# Monitor.net
KiCad netlist of a schematic drawn in EAGLE
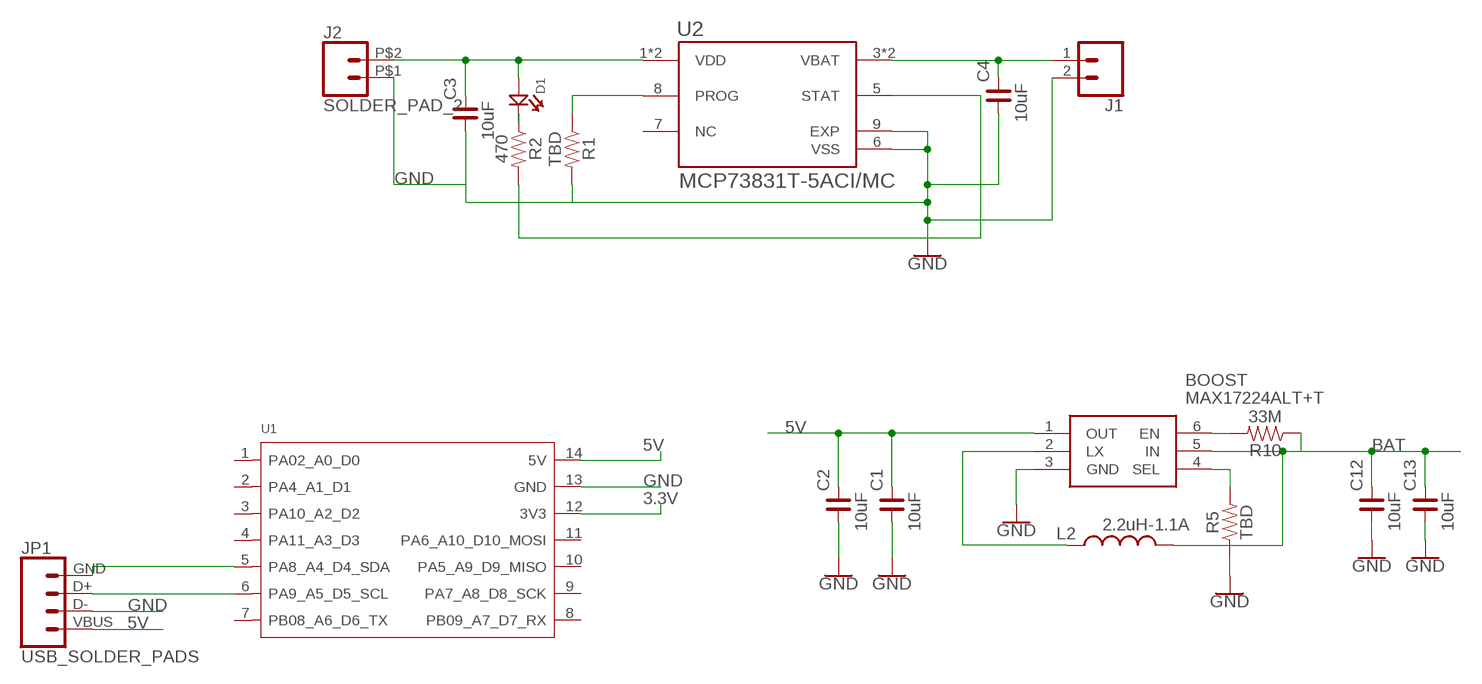
[diagram p0: schematic, sheet 1]

(export (version "E")
  (design (tool "Eeschema 10.0.6"))
  (components
    (comp (ref "BOOST")
      (value "MAX17224ALT+T")
      (footprint "eagle-import:MAX17220ALT")
      (fields (field (name "MOUSER_PART_NUMBER") "700-MAX17224ALT+T"))
      (libsource (lib "eagle-import") (part "MAX17224ALT+T"))
    )
    (comp (ref "C1")
      (value "10uF")
      (footprint "eagle-import:C0805")
      (libsource (lib "eagle-import") (part "C_0805"))
    )
    (comp (ref "C2")
      (value "10uF")
      (footprint "eagle-import:C0805")
      (libsource (lib "eagle-import") (part "C_0805"))
    )
    (comp (ref "C3")
      (value "10uF")
      (footprint "eagle-import:C0805")
      (libsource (lib "eagle-import") (part "C_0805"))
    )
    (comp (ref "C4")
      (value "10uF")
      (footprint "eagle-import:C0805")
      (libsource (lib "eagle-import") (part "C_0805"))
    )
    (comp (ref "C12")
      (value "10uF")
      (footprint "eagle-import:C0805")
      (libsource (lib "eagle-import") (part "C_0805"))
    )
    (comp (ref "C13")
      (value "10uF")
      (footprint "eagle-import:C0805")
      (libsource (lib "eagle-import") (part "C_0805"))
    )
    (comp (ref "D1")
      (value "LED0603")
      (footprint "eagle-import:LED-0603")
      (libsource (lib "eagle-import") (part "LED0603"))
    )
    (comp (ref "J1")
      (value "CONN_021X02_NO_SILK")
      (footprint "eagle-import:1X02_NO_SILK")
      (libsource (lib "eagle-import") (part "CONN_021X02_NO_SILK"))
    )
    (comp (ref "J2")
      (value "SOLDER_PAD_2")
      (footprint "eagle-import:SOLDER_PAD_2")
      (libsource (lib "eagle-import") (part "SOLDER_PAD_2"))
    )
    (comp (ref "JP1")
      (value "USB_SOLDER_PADS")
      (footprint "eagle-import:USB-SOLDER-PADS")
      (libsource (lib "eagle-import") (part "USB_SOLDER_PADS"))
    )
    (comp (ref "L2")
      (value "2.2uH-1.1A")
      (footprint "eagle-import:LPS4012")
      (fields
        (field (name "MF") "Coilcraft")
        (field (name "MPN") "LPS4012-103MRB")
        (field (name "MF_1") "BOURNS")
        (field (name "MPN_1") "SRN2009T-100M")
      )
      (libsource (lib "eagle-import") (part "L3.9X3.9_10UH_0.55A"))
    )
    (comp (ref "R1")
      (value "TBD")
      (footprint "eagle-import:0603")
      (libsource (lib "eagle-import") (part "2.2KOHM-0603-1/10W-1%"))
    )
    (comp (ref "R2")
      (value "470")
      (footprint "eagle-import:0603")
      (libsource (lib "eagle-import") (part "2.2KOHM-0603-1/10W-1%"))
    )
    (comp (ref "R5")
      (value "TBD")
      (footprint "eagle-import:0603")
      (libsource (lib "eagle-import") (part "2.2KOHM-0603-1/10W-1%"))
    )
    (comp (ref "R10")
      (value "33M")
      (footprint "eagle-import:0603")
      (libsource (lib "eagle-import") (part "2.2KOHM-0603-1/10W-1%"))
    )
    (comp (ref "U1")
      (value "MOUDLE-SEEEDUINO-XIAO")
      (footprint "eagle-import:MOUDLE14P-2.54-21X17.8MM")
      (libsource (lib "eagle-import") (part "MOUDLE-SEEEDUINO-XIAO"))
    )
    (comp (ref "U2")
      (value "MCP73831T-5ACI/MC")
      (footprint "eagle-import:SON50P200X300X100-9N")
      (fields (field (name "MF") "Microchip Technology") (field (name "MP") "MCP73831T5ACIMC"))
      (libsource (lib "eagle-import") (part "MCP73831T-5ACI/MC"))
    )
  )
  (nets
    (net (code "1") (name "/3.3V") (class "Default")
      (node (ref "U1") (pin "12") (pinfunction "3V3_12") (pintype "bidirectional"))
    )
    (net (code "2") (name "/5V") (class "Default")
      (node (ref "BOOST") (pin "1") (pinfunction "OUT_1") (pintype "bidirectional"))
      (node (ref "C1") (pin "2") (pinfunction "2_2") (pintype "passive"))
      (node (ref "C2") (pin "2") (pinfunction "2_2") (pintype "passive"))
      (node (ref "JP1") (pin "VBUS") (pinfunction "1_VBUS") (pintype "passive"))
      (node (ref "U1") (pin "14") (pinfunction "5V_14") (pintype "bidirectional"))
    )
    (net (code "3") (name "/BAT") (class "Default")
      (node (ref "BOOST") (pin "5") (pinfunction "IN_5") (pintype "bidirectional"))
      (node (ref "C12") (pin "2") (pinfunction "2_2") (pintype "passive"))
      (node (ref "C13") (pin "2") (pinfunction "2_2") (pintype "passive"))
      (node (ref "L2") (pin "2") (pinfunction "2_2") (pintype "passive"))
      (node (ref "R10") (pin "1") (pinfunction "1_1") (pintype "passive"))
    )
    (net (code "4") (name "GND") (class "Default")
      (node (ref "BOOST") (pin "3") (pinfunction "GND_3") (pintype "bidirectional"))
      (node (ref "C1") (pin "1") (pinfunction "1_1") (pintype "passive"))
      (node (ref "C12") (pin "1") (pinfunction "1_1") (pintype "passive"))
      (node (ref "C13") (pin "1") (pinfunction "1_1") (pintype "passive"))
      (node (ref "C2") (pin "1") (pinfunction "1_1") (pintype "passive"))
      (node (ref "C3") (pin "1") (pinfunction "1_1") (pintype "passive"))
      (node (ref "C4") (pin "1") (pinfunction "1_1") (pintype "passive"))
      (node (ref "J1") (pin "2") (pinfunction "2_2") (pintype "passive"))
      (node (ref "J2") (pin "P$1") (pinfunction "1_P$1") (pintype "passive"))
      (node (ref "JP1") (pin "D-") (pinfunction "2_D-") (pintype "passive"))
      (node (ref "R1") (pin "2") (pinfunction "2_2") (pintype "passive"))
      (node (ref "R5") (pin "1") (pinfunction "1_1") (pintype "passive"))
      (node (ref "U1") (pin "13") (pinfunction "GND_13") (pintype "bidirectional"))
      (node (ref "U2") (pin "6") (pinfunction "VSS_6") (pintype "power_in"))
      (node (ref "U2") (pin "9") (pinfunction "EXP_9") (pintype "power_in"))
    )
    (net (code "5") (name "Net-(BOOST-EN)") (class "Default")
      (node (ref "BOOST") (pin "6") (pinfunction "EN_6") (pintype "bidirectional"))
      (node (ref "R10") (pin "2") (pinfunction "2_2") (pintype "passive"))
    )
    (net (code "6") (name "Net-(BOOST-LX)") (class "Default")
      (node (ref "BOOST") (pin "2") (pinfunction "LX_2") (pintype "bidirectional"))
      (node (ref "L2") (pin "1") (pinfunction "1_1") (pintype "passive"))
    )
    (net (code "7") (name "Net-(BOOST-SEL)") (class "Default")
      (node (ref "BOOST") (pin "4") (pinfunction "SEL_4") (pintype "bidirectional"))
      (node (ref "R5") (pin "2") (pinfunction "2_2") (pintype "passive"))
    )
    (net (code "8") (name "Net-(C4-Pad2)") (class "Default")
      (node (ref "C4") (pin "2") (pinfunction "2_2") (pintype "passive"))
      (node (ref "J1") (pin "1") (pinfunction "1_1") (pintype "passive"))
      (node (ref "U2") (pin "3") (pinfunction "VBAT_3") (pintype "output"))
      (node (ref "U2") (pin "4") (pinfunction "VBAT_4") (pintype "output"))
    )
    (net (code "9") (name "Net-(D1-Pad-)") (class "Default")
      (node (ref "D1") (pin "-") (pinfunction "-_-") (pintype "passive"))
      (node (ref "R2") (pin "1") (pinfunction "1_1") (pintype "passive"))
    )
    (net (code "10") (name "Net-(J2-2)") (class "Default")
      (node (ref "C3") (pin "2") (pinfunction "2_2") (pintype "passive"))
      (node (ref "D1") (pin "+") (pinfunction "+_+") (pintype "passive"))
      (node (ref "J2") (pin "P$2") (pinfunction "2_P$2") (pintype "passive"))
      (node (ref "U2") (pin "1") (pinfunction "VDD_1") (pintype "input"))
      (node (ref "U2") (pin "2") (pinfunction "VDD_2") (pintype "input"))
    )
    (net (code "11") (name "Net-(JP1-3)") (class "Default")
      (node (ref "JP1") (pin "D+") (pinfunction "3_D+") (pintype "passive"))
      (node (ref "U1") (pin "6") (pinfunction "PA9_A5_D5_SCL_6") (pintype "bidirectional"))
    )
    (net (code "12") (name "Net-(JP1-4)") (class "Default")
      (node (ref "JP1") (pin "GND") (pinfunction "4_GND") (pintype "passive"))
      (node (ref "U1") (pin "5") (pinfunction "PA8_A4_D4_SDA_5") (pintype "bidirectional"))
    )
    (net (code "13") (name "Net-(U2-PROG)") (class "Default")
      (node (ref "R1") (pin "1") (pinfunction "1_1") (pintype "passive"))
      (node (ref "U2") (pin "8") (pinfunction "PROG_8") (pintype "input"))
    )
    (net (code "14") (name "Net-(U2-STAT)") (class "Default")
      (node (ref "R2") (pin "2") (pinfunction "2_2") (pintype "passive"))
      (node (ref "U2") (pin "5") (pinfunction "STAT_5") (pintype "output"))
    )
    (net (code "15") (name "unconnected-(U1-PA02_A0_D0-Pad1)") (class "Default")
      (node (ref "U1") (pin "1") (pinfunction "PA02_A0_D0_1") (pintype "bidirectional"))
    )
    (net (code "16") (name "unconnected-(U1-PA4_A1_D1-Pad2)") (class "Default")
      (node (ref "U1") (pin "2") (pinfunction "PA4_A1_D1_2") (pintype "bidirectional"))
    )
    (net (code "17") (name "unconnected-(U1-PA5_A9_D9_MISO-Pad10)") (class "Default")
      (node (ref "U1") (pin "10") (pinfunction "PA5_A9_D9_MISO_10") (pintype "bidirectional"))
    )
    (net (code "18") (name "unconnected-(U1-PA6_A10_D10_MOSI-Pad11)") (class "Default")
      (node (ref "U1") (pin "11") (pinfunction "PA6_A10_D10_MOSI_11") (pintype "bidirectional"))
    )
    (net (code "19") (name "unconnected-(U1-PA7_A8_D8_SCK-Pad9)") (class "Default")
      (node (ref "U1") (pin "9") (pinfunction "PA7_A8_D8_SCK_9") (pintype "bidirectional"))
    )
    (net (code "20") (name "unconnected-(U1-PA10_A2_D2-Pad3)") (class "Default")
      (node (ref "U1") (pin "3") (pinfunction "PA10_A2_D2_3") (pintype "bidirectional"))
    )
    (net (code "21") (name "unconnected-(U1-PA11_A3_D3-Pad4)") (class "Default")
      (node (ref "U1") (pin "4") (pinfunction "PA11_A3_D3_4") (pintype "bidirectional"))
    )
    (net (code "22") (name "unconnected-(U1-PB08_A6_D6_TX-Pad7)") (class "Default")
      (node (ref "U1") (pin "7") (pinfunction "PB08_A6_D6_TX_7") (pintype "bidirectional"))
    )
    (net (code "23") (name "unconnected-(U1-PB09_A7_D7_RX-Pad8)") (class "Default")
      (node (ref "U1") (pin "8") (pinfunction "PB09_A7_D7_RX_8") (pintype "bidirectional"))
    )
    (net (code "24") (name "unconnected-(U2-NC-Pad7)") (class "Default")
      (node (ref "U2") (pin "7") (pinfunction "NC_7") (pintype "no_connect"))
    )
  )
)
